# MCU.net
KiCad netlist of a schematic drawn in Altium Designer
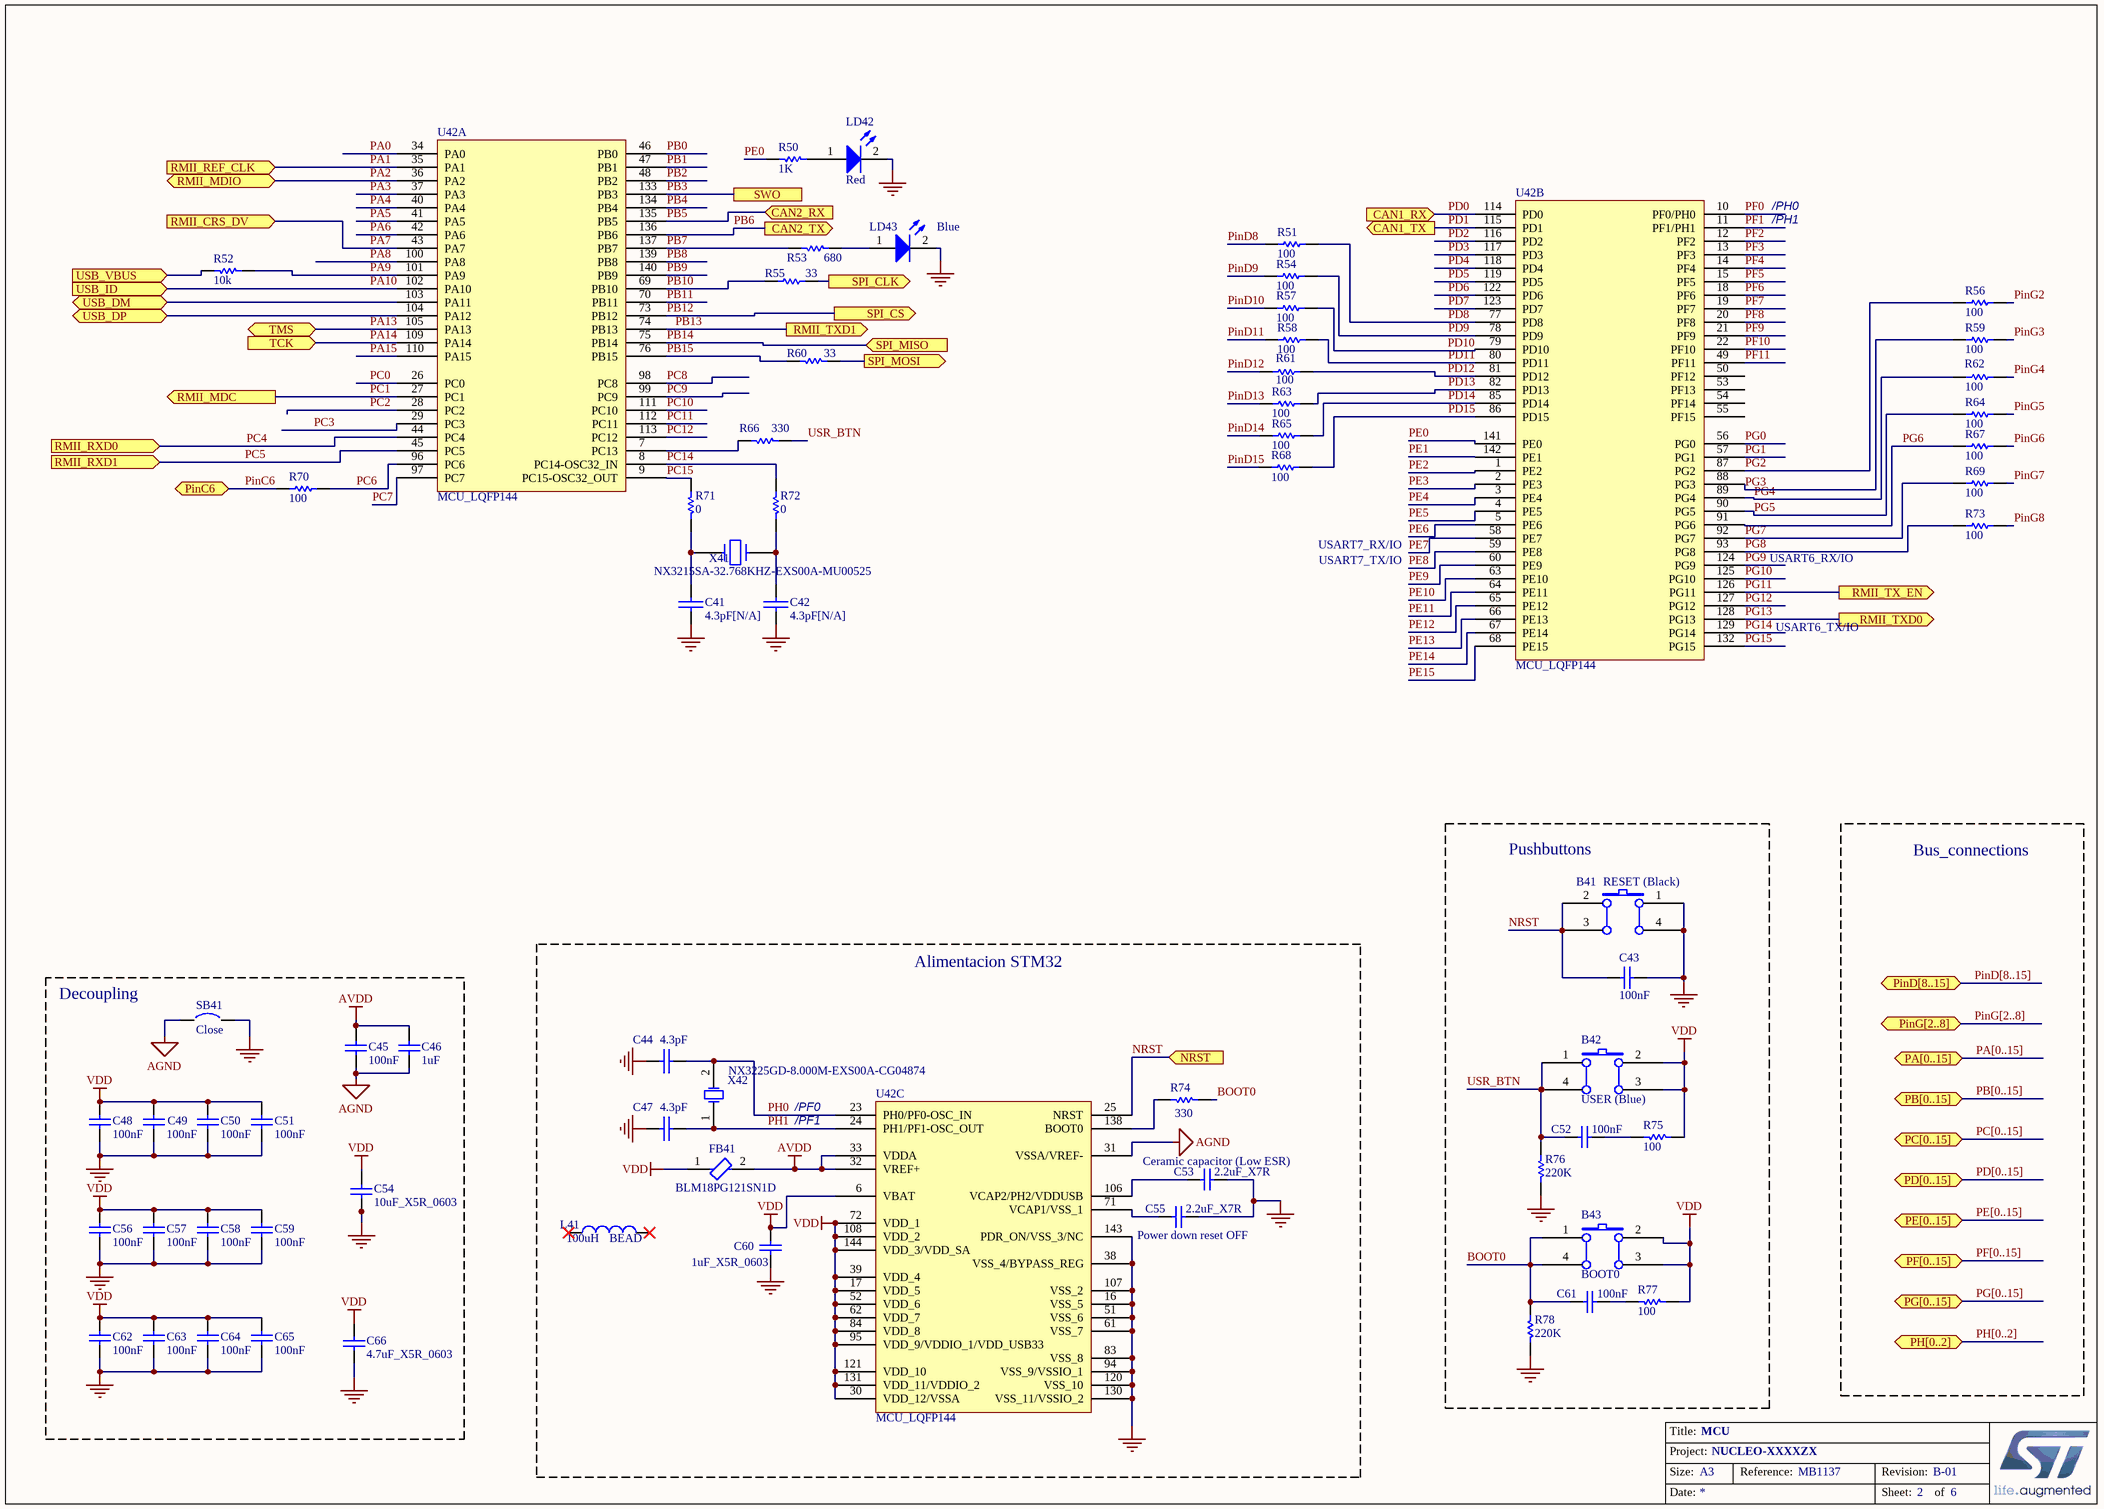
[diagram p0: MCU.SchDoc]

(export (version "E")
  (design (tool "Eeschema 10.0.6"))
  (components
    (comp (ref "B41")
      (value "RESET (Black)")
      (footprint "PB-6X6mm-Black")
      (description "SE PUSHBUTTON")
      (libsource (lib "Documents") (part "SW PUSHBUTTON"))
    )
    (comp (ref "B42")
      (value "USER (Blue)")
      (footprint "PB-6X6mm-Blue")
      (description "SE PUSHBUTTON")
      (libsource (lib "Documents") (part "SW PUSHBUTTON"))
    )
    (comp (ref "B43")
      (value "BOOT0")
      (footprint "PB-6X6mm-Blue")
      (description "SE PUSHBUTTON")
      (libsource (lib "Documents") (part "SW PUSHBUTTON"))
    )
    (comp (ref "C41")
      (value "4.3pF[N/A]")
      (footprint "0603C")
      (description "Capacitor")
      (libsource (lib "MB1137") (part "CAP"))
    )
    (comp (ref "C42")
      (value "4.3pF[N/A]")
      (footprint "0603C")
      (description "Capacitor")
      (libsource (lib "MB1137") (part "CAP"))
    )
    (comp (ref "C43")
      (value "100nF")
      (footprint "0603C")
      (description "Capacitor")
      (fields (field (name "PUBLISHER") "Altium Limited"))
      (libsource (lib "Miscellaneous Devices") (part "CAP"))
    )
    (comp (ref "C44")
      (value "4.3pF")
      (footprint "0603C")
      (description "Capacitor")
      (libsource (lib "MB1137") (part "CAP"))
    )
    (comp (ref "C45")
      (value "100nF")
      (footprint "0603C")
      (description "Capacitor")
      (fields (field (name "PUBLISHER") "Altium Limited"))
      (libsource (lib "Miscellaneous Devices") (part "Cap"))
    )
    (comp (ref "C46")
      (value "1uF")
      (footprint "0603C")
      (description "Capacitor")
      (fields (field (name "PUBLISHER") "Altium Limited"))
      (libsource (lib "Miscellaneous Devices") (part "Cap"))
    )
    (comp (ref "C47")
      (value "4.3pF")
      (footprint "0603C")
      (description "Capacitor")
      (libsource (lib "MB1137") (part "CAP"))
    )
    (comp (ref "C48")
      (value "100nF")
      (footprint "0603C")
      (description "Capacitor")
      (fields (field (name "PUBLISHER") "Altium Limited"))
      (libsource (lib "Miscellaneous Devices") (part "Cap"))
    )
    (comp (ref "C49")
      (value "100nF")
      (footprint "0603C")
      (description "Capacitor")
      (fields (field (name "PUBLISHER") "Altium Limited"))
      (libsource (lib "Miscellaneous Devices") (part "Cap"))
    )
    (comp (ref "C50")
      (value "100nF")
      (footprint "0603C")
      (description "Capacitor")
      (fields (field (name "PUBLISHER") "Altium Limited"))
      (libsource (lib "Miscellaneous Devices") (part "Cap"))
    )
    (comp (ref "C51")
      (value "100nF")
      (footprint "0603C")
      (description "Capacitor")
      (fields (field (name "PUBLISHER") "Altium Limited"))
      (libsource (lib "Miscellaneous Devices") (part "Cap"))
    )
    (comp (ref "C52")
      (value "100nF")
      (footprint "0603C")
      (description "Capacitor")
      (fields (field (name "PUBLISHER") "Altium Limited"))
      (libsource (lib "") (part "CAP_1"))
    )
    (comp (ref "C53")
      (value "2.2uF_X7R")
      (footprint "TAN-A")
      (description "Capacitor,2.2uF,16V, X7R,10%,0805,YAGEO")
      (libsource (lib "MCD_TOOLS") (part "Cap_2.2uF_X7R_10%_0805"))
    )
    (comp (ref "C54")
      (value "10uF_X5R_0603")
      (footprint "0603C")
      (description "0603  X5R 4.7uF")
      (fields (field (name "TOLERANCE") "10%"))
      (libsource (lib "MB963_1") (part "CAP SMD 0603  X5R 1µF 25V 10%"))
    )
    (comp (ref "C55")
      (value "2.2uF_X7R")
      (footprint "TAN-A")
      (description "Capacitor,2.2uF,16V, X7R,10%,0805,YAGEO")
      (libsource (lib "MCD_TOOLS") (part "Cap_2.2uF_X7R_10%_0805"))
    )
    (comp (ref "C56")
      (value "100nF")
      (footprint "0603C")
      (description "Capacitor")
      (fields (field (name "PUBLISHER") "Altium Limited"))
      (libsource (lib "Miscellaneous Devices") (part "Cap"))
    )
    (comp (ref "C57")
      (value "100nF")
      (footprint "0603C")
      (description "Capacitor")
      (fields (field (name "PUBLISHER") "Altium Limited"))
      (libsource (lib "Miscellaneous Devices") (part "Cap"))
    )
    (comp (ref "C58")
      (value "100nF")
      (footprint "0603C")
      (description "Capacitor")
      (fields (field (name "PUBLISHER") "Altium Limited"))
      (libsource (lib "Miscellaneous Devices") (part "Cap"))
    )
    (comp (ref "C59")
      (value "100nF")
      (footprint "0603C")
      (description "Capacitor")
      (fields (field (name "PUBLISHER") "Altium Limited"))
      (libsource (lib "Miscellaneous Devices") (part "Cap"))
    )
    (comp (ref "C60")
      (value "1uF_X5R_0603")
      (footprint "0603C")
      (description "0603  X5R 1µF")
      (fields (field (name "TOLERANCE") "10%"))
      (libsource (lib "MB963_1") (part "CAP SMD 0603  X5R 1µF 25V 10%"))
    )
    (comp (ref "C61")
      (value "100nF")
      (footprint "0603C")
      (description "Capacitor")
      (fields (field (name "PUBLISHER") "Altium Limited"))
      (libsource (lib "") (part "CAP_1"))
    )
    (comp (ref "C62")
      (value "100nF")
      (footprint "0603C")
      (description "Capacitor")
      (fields (field (name "PUBLISHER") "Altium Limited"))
      (libsource (lib "Miscellaneous Devices") (part "Cap"))
    )
    (comp (ref "C63")
      (value "100nF")
      (footprint "0603C")
      (description "Capacitor")
      (fields (field (name "PUBLISHER") "Altium Limited"))
      (libsource (lib "Miscellaneous Devices") (part "Cap"))
    )
    (comp (ref "C64")
      (value "100nF")
      (footprint "0603C")
      (description "Capacitor")
      (fields (field (name "PUBLISHER") "Altium Limited"))
      (libsource (lib "Miscellaneous Devices") (part "Cap"))
    )
    (comp (ref "C65")
      (value "100nF")
      (footprint "0603C")
      (description "Capacitor")
      (fields (field (name "PUBLISHER") "Altium Limited"))
      (libsource (lib "Miscellaneous Devices") (part "Cap"))
    )
    (comp (ref "C66")
      (value "4.7uF_X5R_0603")
      (footprint "0603C")
      (description "0603  X5R 4.7uF")
      (fields (field (name "TOLERANCE") "10%"))
      (libsource (lib "MB963_1") (part "CAP SMD 0603  X5R 1µF 25V 10%"))
    )
    (comp (ref "FB41")
      (value "BLM18PG121SN1D")
      (footprint "FP-BLM18-0_15-t0_8-IPC_A")
      (description "Chip Ferrite Bead, 0603, 120Ω @ 100MHz, 0.05Ω, 25%, 2A")
      (fields (field (name "TOLERANCE") "25%"))
      (libsource (lib "Altium Content Vault") (part "5f30dd21d616792df468990f7003faa"))
    )
    (comp (ref "L41")
      (value "BEAD")
      (description "Inductor")
      (fields (field (name "ALTIUM_VALUE") "100uH") (field (name "PUBLISHER") "Altium Limited"))
      (libsource (lib "Miscellaneous Devices") (part "Inductor"))
    )
    (comp (ref "LD42")
      (value "Red")
      (footprint "0603D-R")
      (description "Typical RED, GREEN, YELLOW, AMBER GaAs LED")
      (fields (field (name "PUBLISHER") "Altium Limited"))
      (libsource (lib "Miscellaneous Devices") (part "LED2"))
    )
    (comp (ref "LD43")
      (value "Blue")
      (footprint "0603D-B")
      (description "Typical RED, GREEN, YELLOW, AMBER GaAs LED")
      (fields (field (name "PUBLISHER") "Altium Limited"))
      (libsource (lib "Miscellaneous Devices") (part "LED2"))
    )
    (comp (ref "R50")
      (value "1K")
      (footprint "0603R")
      (description "Resistor")
      (fields (field (name "PUBLISHER") "Altium Limited"))
      (libsource (lib "Miscellaneous Devices") (part "Res1"))
    )
    (comp (ref "R51")
      (value "100")
      (footprint "0603R")
      (description "Resistor 0402 / 0603 / 0805")
      (libsource (lib "MB1137") (part "Resistor_ST"))
    )
    (comp (ref "R52")
      (value "10k")
      (footprint "0603R")
      (description "Resistor")
      (fields (field (name "PUBLISHER") "Altium Limited"))
      (libsource (lib "Miscellaneous Devices") (part "Res1"))
    )
    (comp (ref "R53")
      (value "680")
      (footprint "0603R")
      (description "Resistor")
      (fields (field (name "PUBLISHER") "Altium Limited"))
      (libsource (lib "Miscellaneous Devices") (part "Res1"))
    )
    (comp (ref "R54")
      (value "100")
      (footprint "0603R")
      (description "Resistor 0402 / 0603 / 0805")
      (libsource (lib "MB1137") (part "Resistor_ST"))
    )
    (comp (ref "R55")
      (value "33")
      (footprint "0603R")
      (description "Resistor")
      (fields (field (name "PUBLISHER") "Altium Limited"))
      (libsource (lib "MB1137") (part "Res1"))
    )
    (comp (ref "R56")
      (value "100")
      (footprint "0603R")
      (description "Resistor 0402 / 0603 / 0805")
      (libsource (lib "MB1137") (part "Resistor_ST"))
    )
    (comp (ref "R57")
      (value "100")
      (footprint "0603R")
      (description "Resistor 0402 / 0603 / 0805")
      (libsource (lib "MB1137") (part "Resistor_ST"))
    )
    (comp (ref "R58")
      (value "100")
      (footprint "0603R")
      (description "Resistor 0402 / 0603 / 0805")
      (libsource (lib "MB1137") (part "Resistor_ST"))
    )
    (comp (ref "R59")
      (value "100")
      (footprint "0603R")
      (description "Resistor 0402 / 0603 / 0805")
      (libsource (lib "MB1137") (part "Resistor_ST"))
    )
    (comp (ref "R60")
      (value "33")
      (footprint "0603R")
      (description "Resistor")
      (fields (field (name "PUBLISHER") "Altium Limited"))
      (libsource (lib "Miscellaneous Devices") (part "Res1"))
    )
    (comp (ref "R61")
      (value "100")
      (footprint "0603R")
      (description "Resistor 0402 / 0603 / 0805")
      (libsource (lib "MB1137") (part "Resistor_ST"))
    )
    (comp (ref "R62")
      (value "100")
      (footprint "0603R")
      (description "Resistor 0402 / 0603 / 0805")
      (libsource (lib "MB1137") (part "Resistor_ST"))
    )
    (comp (ref "R63")
      (value "100")
      (footprint "0603R")
      (description "Resistor 0402 / 0603 / 0805")
      (libsource (lib "MB1137") (part "Resistor_ST"))
    )
    (comp (ref "R64")
      (value "100")
      (footprint "0603R")
      (description "Resistor 0402 / 0603 / 0805")
      (libsource (lib "MB1137") (part "Resistor_ST"))
    )
    (comp (ref "R65")
      (value "100")
      (footprint "0603R")
      (description "Resistor 0402 / 0603 / 0805")
      (libsource (lib "MB1137") (part "Resistor_ST"))
    )
    (comp (ref "R66")
      (value "330")
      (footprint "0603R")
      (description "Resistor")
      (fields (field (name "PUBLISHER") "Altium Limited"))
      (libsource (lib "Miscellaneous Devices") (part "Res1"))
    )
    (comp (ref "R67")
      (value "100")
      (footprint "0603R")
      (description "Resistor 0402 / 0603 / 0805")
      (libsource (lib "MB1137") (part "Resistor_ST"))
    )
    (comp (ref "R68")
      (value "100")
      (footprint "0603R")
      (description "Resistor 0402 / 0603 / 0805")
      (libsource (lib "MB1137") (part "Resistor_ST"))
    )
    (comp (ref "R69")
      (value "100")
      (footprint "0603R")
      (description "Resistor 0402 / 0603 / 0805")
      (libsource (lib "MB1137") (part "Resistor_ST"))
    )
    (comp (ref "R70")
      (value "100")
      (footprint "0603R")
      (description "Resistor 0402 / 0603 / 0805")
      (libsource (lib "MB1137") (part "Resistor_ST"))
    )
    (comp (ref "R71")
      (value "0")
      (footprint "0603R")
      (description "Resistor")
      (fields (field (name "PUBLISHER") "Altium Limited"))
      (libsource (lib "Miscellaneous Devices") (part "Res1"))
    )
    (comp (ref "R72")
      (value "0")
      (footprint "0603R")
      (description "Resistor")
      (fields (field (name "PUBLISHER") "Altium Limited"))
      (libsource (lib "Miscellaneous Devices") (part "Res1"))
    )
    (comp (ref "R73")
      (value "100")
      (footprint "0603R")
      (description "Resistor 0402 / 0603 / 0805")
      (libsource (lib "MB1137") (part "Resistor_ST"))
    )
    (comp (ref "R74")
      (value "330")
      (footprint "0603R")
      (description "Resistor")
      (fields (field (name "PUBLISHER") "Altium Limited"))
      (libsource (lib "Miscellaneous Devices") (part "Res1"))
    )
    (comp (ref "R75")
      (value "100")
      (footprint "0603R")
      (description "Resistor")
      (fields (field (name "PUBLISHER") "Altium Limited"))
      (libsource (lib "Miscellaneous Devices") (part "Res1"))
    )
    (comp (ref "R76")
      (value "220K")
      (footprint "0603R")
      (description "Resistor")
      (fields (field (name "PUBLISHER") "Altium Limited"))
      (libsource (lib "Miscellaneous Devices") (part "res1"))
    )
    (comp (ref "R77")
      (value "100")
      (footprint "0603R")
      (description "Resistor")
      (fields (field (name "PUBLISHER") "Altium Limited"))
      (libsource (lib "Miscellaneous Devices") (part "Res1"))
    )
    (comp (ref "R78")
      (value "220K")
      (footprint "0603R")
      (description "Resistor")
      (fields (field (name "PUBLISHER") "Altium Limited"))
      (libsource (lib "Miscellaneous Devices") (part "res1"))
    )
    (comp (ref "SB41")
      (value "Close")
      (footprint "SB_0603")
      (description "Circuit Breaker")
      (fields (field (name "PUBLISHER") "Altium Limited"))
      (libsource (lib "MB1137") (part "Circuit Breaker"))
    )
    (comp (ref "U42")
      (value "MCU_LQFP144")
      (footprint "LQFP144_0R5_SKT - sin_zocalo_UWU")
      (libsource (lib "MB1137") (part "MCU_LQFP144"))
    )
    (comp (ref "X41")
      (value "NX3215SA-32.768KHZ-EXS00A-MU00525")
      (footprint "XTAL_2SM_3R2X1R5")
      (description "Crystal")
      (libsource (lib "MB1167") (part "CRYSTAL_32K"))
    )
    (comp (ref "X42")
      (value "NX3225GD-8.000M-EXS00A-CG04874")
      (footprint "OSC_2SM_3R2x2R5")
      (description "Crystal Oscillator")
      (fields (field (name "PUBLISHER") "Altium Limited"))
      (libsource (lib "MB963_1") (part "XTAL"))
    )
  )
  (nets
    (net (code "9") (name "/BOOT0") (class "Default")
      (node (ref "B43") (pin "1") (pinfunction "A0_1") (pintype "passive"))
      (node (ref "B43") (pin "4") (pinfunction "A1_4") (pintype "passive"))
      (node (ref "C61") (pin "2") (pinfunction "2_2") (pintype "passive"))
      (node (ref "R74") (pin "2") (pinfunction "2_2") (pintype "passive"))
      (node (ref "R78") (pin "1") (pinfunction "1_1") (pintype "passive"))
    )
    (net (code "10") (name "/NRST") (class "Default")
      (node (ref "B41") (pin "2") (pinfunction "B0_2") (pintype "passive"))
      (node (ref "B41") (pin "3") (pinfunction "B1_3") (pintype "passive"))
      (node (ref "C43") (pin "2") (pinfunction "2_2") (pintype "passive"))
      (node (ref "U42") (pin "25") (pinfunction "NRST_25") (pintype "passive"))
    )
    (net (code "11") (name "/PA0") (class "Default")
      (node (ref "U42") (pin "34") (pinfunction "PA0_34") (pintype "passive"))
    )
    (net (code "12") (name "/PA1") (class "Default")
      (node (ref "U42") (pin "35") (pinfunction "PA1_35") (pintype "passive"))
    )
    (net (code "13") (name "/PA2") (class "Default")
      (node (ref "U42") (pin "36") (pinfunction "PA2_36") (pintype "passive"))
    )
    (net (code "14") (name "/PA3") (class "Default")
      (node (ref "U42") (pin "37") (pinfunction "PA3_37") (pintype "passive"))
    )
    (net (code "15") (name "/PA4") (class "Default")
      (node (ref "U42") (pin "40") (pinfunction "PA4_40") (pintype "passive"))
    )
    (net (code "16") (name "/PA5") (class "Default")
      (node (ref "U42") (pin "41") (pinfunction "PA5_41") (pintype "passive"))
    )
    (net (code "17") (name "/PA6") (class "Default")
      (node (ref "U42") (pin "42") (pinfunction "PA6_42") (pintype "passive"))
    )
    (net (code "18") (name "/PA7") (class "Default")
      (node (ref "U42") (pin "43") (pinfunction "PA7_43") (pintype "passive"))
    )
    (net (code "19") (name "/PA8") (class "Default")
      (node (ref "U42") (pin "100") (pinfunction "PA8_100") (pintype "passive"))
    )
    (net (code "20") (name "/PA9") (class "Default")
      (node (ref "R52") (pin "2") (pinfunction "2_2") (pintype "passive"))
      (node (ref "U42") (pin "101") (pinfunction "PA9_101") (pintype "passive"))
    )
    (net (code "21") (name "/PA10") (class "Default")
      (node (ref "U42") (pin "102") (pinfunction "PA10_102") (pintype "passive"))
    )
    (net (code "22") (name "/PA13") (class "Default")
      (node (ref "U42") (pin "105") (pinfunction "PA13_105") (pintype "passive"))
    )
    (net (code "23") (name "/PA14") (class "Default")
      (node (ref "U42") (pin "109") (pinfunction "PA14_109") (pintype "passive"))
    )
    (net (code "24") (name "/PA15") (class "Default")
      (node (ref "U42") (pin "110") (pinfunction "PA15_110") (pintype "passive"))
    )
    (net (code "26") (name "/PB0") (class "Default")
      (node (ref "U42") (pin "46") (pinfunction "PB0_46") (pintype "passive"))
    )
    (net (code "27") (name "/PB1") (class "Default")
      (node (ref "U42") (pin "47") (pinfunction "PB1_47") (pintype "passive"))
    )
    (net (code "28") (name "/PB2") (class "Default")
      (node (ref "U42") (pin "48") (pinfunction "PB2_48") (pintype "passive"))
    )
    (net (code "29") (name "/PB3") (class "Default")
      (node (ref "U42") (pin "133") (pinfunction "PB3_133") (pintype "passive"))
    )
    (net (code "30") (name "/PB4") (class "Default")
      (node (ref "U42") (pin "134") (pinfunction "PB4_134") (pintype "passive"))
    )
    (net (code "31") (name "/PB5") (class "Default")
      (node (ref "U42") (pin "135") (pinfunction "PB5_135") (pintype "passive"))
    )
    (net (code "32") (name "/PB6") (class "Default")
      (node (ref "U42") (pin "136") (pinfunction "PB6_136") (pintype "passive"))
    )
    (net (code "33") (name "/PB7") (class "Default")
      (node (ref "R53") (pin "1") (pinfunction "1_1") (pintype "passive"))
      (node (ref "U42") (pin "137") (pinfunction "PB7_137") (pintype "passive"))
    )
    (net (code "34") (name "/PB8") (class "Default")
      (node (ref "U42") (pin "139") (pinfunction "PB8_139") (pintype "passive"))
    )
    (net (code "35") (name "/PB9") (class "Default")
      (node (ref "U42") (pin "140") (pinfunction "PB9_140") (pintype "passive"))
    )
    (net (code "36") (name "/PB10") (class "Default")
      (node (ref "R55") (pin "1") (pinfunction "1_1") (pintype "passive"))
      (node (ref "U42") (pin "69") (pinfunction "PB10_69") (pintype "passive"))
    )
    (net (code "37") (name "/PB11") (class "Default")
      (node (ref "U42") (pin "70") (pinfunction "PB11_70") (pintype "passive"))
    )
    (net (code "38") (name "/PB12") (class "Default")
      (node (ref "U42") (pin "73") (pinfunction "PB12_73") (pintype "passive"))
    )
    (net (code "39") (name "/PB13") (class "Default")
      (node (ref "U42") (pin "74") (pinfunction "PB13_74") (pintype "passive"))
    )
    (net (code "40") (name "/PB14") (class "Default")
      (node (ref "U42") (pin "75") (pinfunction "PB14_75") (pintype "passive"))
    )
    (net (code "41") (name "/PB15") (class "Default")
      (node (ref "R60") (pin "1") (pinfunction "1_1") (pintype "passive"))
      (node (ref "U42") (pin "76") (pinfunction "PB15_76") (pintype "passive"))
    )
    (net (code "43") (name "/PC0") (class "Default")
      (node (ref "U42") (pin "26") (pinfunction "PC0_26") (pintype "passive"))
    )
    (net (code "44") (name "/PC1") (class "Default")
      (node (ref "U42") (pin "27") (pinfunction "PC1_27") (pintype "passive"))
    )
    (net (code "45") (name "/PC2") (class "Default")
      (node (ref "U42") (pin "28") (pinfunction "PC2_28") (pintype "passive"))
    )
    (net (code "46") (name "/PC3") (class "Default")
      (node (ref "U42") (pin "29") (pinfunction "PC3_29") (pintype "passive"))
    )
    (net (code "47") (name "/PC4") (class "Default")
      (node (ref "U42") (pin "44") (pinfunction "PC4_44") (pintype "passive"))
    )
    (net (code "48") (name "/PC5") (class "Default")
      (node (ref "U42") (pin "45") (pinfunction "PC5_45") (pintype "passive"))
    )
    (net (code "49") (name "/PC6") (class "Default")
      (node (ref "R70") (pin "2") (pinfunction "2_2") (pintype "passive"))
      (node (ref "U42") (pin "96") (pinfunction "PC6_96") (pintype "passive"))
    )
    (net (code "50") (name "/PC7") (class "Default")
      (node (ref "U42") (pin "97") (pinfunction "PC7_97") (pintype "passive"))
    )
    (net (code "51") (name "/PC8") (class "Default")
      (node (ref "U42") (pin "98") (pinfunction "PC8_98") (pintype "passive"))
    )
    (net (code "52") (name "/PC9") (class "Default")
      (node (ref "U42") (pin "99") (pinfunction "PC9_99") (pintype "passive"))
    )
    (net (code "53") (name "/PC10") (class "Default")
      (node (ref "U42") (pin "111") (pinfunction "PC10_111") (pintype "passive"))
    )
    (net (code "54") (name "/PC11") (class "Default")
      (node (ref "U42") (pin "112") (pinfunction "PC11_112") (pintype "passive"))
    )
    (net (code "55") (name "/PC12") (class "Default")
      (node (ref "U42") (pin "113") (pinfunction "PC12_113") (pintype "passive"))
    )
    (net (code "56") (name "/PC14") (class "Default")
      (node (ref "R72") (pin "2") (pinfunction "2_2") (pintype "passive"))
      (node (ref "U42") (pin "8") (pinfunction "PC14-OSC32_IN_8") (pintype "passive"))
    )
    (net (code "57") (name "/PC15") (class "Default")
      (node (ref "R71") (pin "2") (pinfunction "2_2") (pintype "passive"))
      (node (ref "U42") (pin "9") (pinfunction "PC15-OSC32_OUT_9") (pintype "passive"))
    )
    (net (code "59") (name "/PD0") (class "Default")
      (node (ref "U42") (pin "114") (pinfunction "PD0_114") (pintype "passive"))
    )
    (net (code "60") (name "/PD1") (class "Default")
      (node (ref "U42") (pin "115") (pinfunction "PD1_115") (pintype "passive"))
    )
    (net (code "61") (name "/PD2") (class "Default")
      (node (ref "U42") (pin "116") (pinfunction "PD2_116") (pintype "passive"))
    )
    (net (code "62") (name "/PD3") (class "Default")
      (node (ref "U42") (pin "117") (pinfunction "PD3_117") (pintype "passive"))
    )
    (net (code "63") (name "/PD4") (class "Default")
      (node (ref "U42") (pin "118") (pinfunction "PD4_118") (pintype "passive"))
    )
    (net (code "64") (name "/PD5") (class "Default")
      (node (ref "U42") (pin "119") (pinfunction "PD5_119") (pintype "passive"))
    )
    (net (code "65") (name "/PD6") (class "Default")
      (node (ref "U42") (pin "122") (pinfunction "PD6_122") (pintype "passive"))
    )
    (net (code "66") (name "/PD7") (class "Default")
      (node (ref "U42") (pin "123") (pinfunction "PD7_123") (pintype "passive"))
    )
    (net (code "67") (name "/PD8") (class "Default")
      (node (ref "R51") (pin "1") (pinfunction "1_1") (pintype "passive"))
      (node (ref "U42") (pin "77") (pinfunction "PD8_77") (pintype "passive"))
    )
    (net (code "68") (name "/PD9") (class "Default")
      (node (ref "R54") (pin "1") (pinfunction "1_1") (pintype "passive"))
      (node (ref "U42") (pin "78") (pinfunction "PD9_78") (pintype "passive"))
    )
    (net (code "69") (name "/PD10") (class "Default")
      (node (ref "R57") (pin "1") (pinfunction "1_1") (pintype "passive"))
      (node (ref "U42") (pin "79") (pinfunction "PD10_79") (pintype "passive"))
    )
    (net (code "70") (name "/PD11") (class "Default")
      (node (ref "R58") (pin "1") (pinfunction "1_1") (pintype "passive"))
      (node (ref "U42") (pin "80") (pinfunction "PD11_80") (pintype "passive"))
    )
    (net (code "71") (name "/PD12") (class "Default")
      (node (ref "R61") (pin "1") (pinfunction "1_1") (pintype "passive"))
      (node (ref "U42") (pin "81") (pinfunction "PD12_81") (pintype "passive"))
    )
    (net (code "72") (name "/PD13") (class "Default")
      (node (ref "R63") (pin "2") (pinfunction "2_2") (pintype "passive"))
      (node (ref "U42") (pin "82") (pinfunction "PD13_82") (pintype "passive"))
    )
    (net (code "73") (name "/PD14") (class "Default")
      (node (ref "R65") (pin "1") (pinfunction "1_1") (pintype "passive"))
      (node (ref "U42") (pin "85") (pinfunction "PD14_85") (pintype "passive"))
    )
    (net (code "74") (name "/PD15") (class "Default")
      (node (ref "R68") (pin "2") (pinfunction "2_2") (pintype "passive"))
      (node (ref "U42") (pin "86") (pinfunction "PD15_86") (pintype "passive"))
    )
    (net (code "76") (name "/PE0") (class "Default")
      (node (ref "R50") (pin "2") (pinfunction "2_2") (pintype "passive"))
      (node (ref "U42") (pin "141") (pinfunction "PE0_141") (pintype "passive"))
    )
    (net (code "77") (name "/PE1") (class "Default")
      (node (ref "U42") (pin "142") (pinfunction "PE1_142") (pintype "passive"))
    )
    (net (code "78") (name "/PE2") (class "Default")
      (node (ref "U42") (pin "1") (pinfunction "PE2_1") (pintype "passive"))
    )
    (net (code "79") (name "/PE3") (class "Default")
      (node (ref "U42") (pin "2") (pinfunction "PE3_2") (pintype "passive"))
    )
    (net (code "80") (name "/PE4") (class "Default")
      (node (ref "U42") (pin "3") (pinfunction "PE4_3") (pintype "passive"))
    )
    (net (code "81") (name "/PE5") (class "Default")
      (node (ref "U42") (pin "4") (pinfunction "PE5_4") (pintype "passive"))
    )
    (net (code "82") (name "/PE6") (class "Default")
      (node (ref "U42") (pin "5") (pinfunction "PE6_5") (pintype "passive"))
    )
    (net (code "83") (name "/PE7") (class "Default")
      (node (ref "U42") (pin "58") (pinfunction "PE7_58") (pintype "passive"))
    )
    (net (code "84") (name "/PE8") (class "Default")
      (node (ref "U42") (pin "59") (pinfunction "PE8_59") (pintype "passive"))
    )
    (net (code "85") (name "/PE9") (class "Default")
      (node (ref "U42") (pin "60") (pinfunction "PE9_60") (pintype "passive"))
    )
    (net (code "86") (name "/PE10") (class "Default")
      (node (ref "U42") (pin "63") (pinfunction "PE10_63") (pintype "passive"))
    )
    (net (code "87") (name "/PE11") (class "Default")
      (node (ref "U42") (pin "64") (pinfunction "PE11_64") (pintype "passive"))
    )
    (net (code "88") (name "/PE12") (class "Default")
      (node (ref "U42") (pin "65") (pinfunction "PE12_65") (pintype "passive"))
    )
    (net (code "89") (name "/PE13") (class "Default")
      (node (ref "U42") (pin "66") (pinfunction "PE13_66") (pintype "passive"))
    )
    (net (code "90") (name "/PE14") (class "Default")
      (node (ref "U42") (pin "67") (pinfunction "PE14_67") (pintype "passive"))
    )
    (net (code "91") (name "/PE15") (class "Default")
      (node (ref "U42") (pin "68") (pinfunction "PE15_68") (pintype "passive"))
    )
    (net (code "93") (name "/PF0") (class "Default")
      (node (ref "U42") (pin "10") (pinfunction "PF0/PH0_10") (pintype "passive"))
    )
    (net (code "94") (name "/PF1") (class "Default")
      (node (ref "U42") (pin "11") (pinfunction "PF1/PH1_11") (pintype "passive"))
    )
    (net (code "95") (name "/PF2") (class "Default")
      (node (ref "U42") (pin "12") (pinfunction "PF2_12") (pintype "passive"))
    )
    (net (code "96") (name "/PF3") (class "Default")
      (node (ref "U42") (pin "13") (pinfunction "PF3_13") (pintype "passive"))
    )
    (net (code "97") (name "/PF4") (class "Default")
      (node (ref "U42") (pin "14") (pinfunction "PF4_14") (pintype "passive"))
    )
    (net (code "98") (name "/PF5") (class "Default")
      (node (ref "U42") (pin "15") (pinfunction "PF5_15") (pintype "passive"))
    )
    (net (code "99") (name "/PF6") (class "Default")
      (node (ref "U42") (pin "18") (pinfunction "PF6_18") (pintype "passive"))
    )
    (net (code "100") (name "/PF7") (class "Default")
      (node (ref "U42") (pin "19") (pinfunction "PF7_19") (pintype "passive"))
    )
    (net (code "101") (name "/PF8") (class "Default")
      (node (ref "U42") (pin "20") (pinfunction "PF8_20") (pintype "passive"))
    )
    (net (code "102") (name "/PF9") (class "Default")
      (node (ref "U42") (pin "21") (pinfunction "PF9_21") (pintype "passive"))
    )
    (net (code "103") (name "/PF10") (class "Default")
      (node (ref "U42") (pin "22") (pinfunction "PF10_22") (pintype "passive"))
    )
    (net (code "104") (name "/PF11") (class "Default")
      (node (ref "U42") (pin "49") (pinfunction "PF11_49") (pintype "passive"))
    )
    (net (code "106") (name "/PG0") (class "Default")
      (node (ref "U42") (pin "56") (pinfunction "PG0_56") (pintype "passive"))
    )
    (net (code "107") (name "/PG1") (class "Default")
      (node (ref "U42") (pin "57") (pinfunction "PG1_57") (pintype "passive"))
    )
    (net (code "108") (name "/PG2") (class "Default")
      (node (ref "R56") (pin "2") (pinfunction "2_2") (pintype "passive"))
      (node (ref "U42") (pin "87") (pinfunction "PG2_87") (pintype "passive"))
    )
    (net (code "109") (name "/PG3") (class "Default")
      (node (ref "R59") (pin "2") (pinfunction "2_2") (pintype "passive"))
      (node (ref "U42") (pin "88") (pinfunction "PG3_88") (pintype "passive"))
    )
    (net (code "110") (name "/PG4") (class "Default")
      (node (ref "R62") (pin "1") (pinfunction "1_1") (pintype "passive"))
      (node (ref "U42") (pin "89") (pinfunction "PG4_89") (pintype "passive"))
    )
    (net (code "111") (name "/PG5") (class "Default")
      (node (ref "R64") (pin "1") (pinfunction "1_1") (pintype "passive"))
      (node (ref "U42") (pin "90") (pinfunction "PG5_90") (pintype "passive"))
    )
    (net (code "112") (name "/PG6") (class "Default")
      (node (ref "R67") (pin "2") (pinfunction "2_2") (pintype "passive"))
      (node (ref "U42") (pin "91") (pinfunction "PG6_91") (pintype "passive"))
    )
    (net (code "113") (name "/PG7") (class "Default")
      (node (ref "R69") (pin "2") (pinfunction "2_2") (pintype "passive"))
      (node (ref "U42") (pin "92") (pinfunction "PG7_92") (pintype "passive"))
    )
    (net (code "114") (name "/PG8") (class "Default")
      (node (ref "R73") (pin "2") (pinfunction "2_2") (pintype "passive"))
      (node (ref "U42") (pin "93") (pinfunction "PG8_93") (pintype "passive"))
    )
    (net (code "115") (name "/PG9") (class "Default")
      (node (ref "U42") (pin "124") (pinfunction "PG9_124") (pintype "passive"))
    )
    (net (code "116") (name "/PG10") (class "Default")
      (node (ref "U42") (pin "125") (pinfunction "PG10_125") (pintype "passive"))
    )
    (net (code "117") (name "/PG11") (class "Default")
      (node (ref "U42") (pin "126") (pinfunction "PG11_126") (pintype "passive"))
    )
    (net (code "118") (name "/PG12") (class "Default")
      (node (ref "U42") (pin "127") (pinfunction "PG12_127") (pintype "passive"))
    )
    (net (code "119") (name "/PG13") (class "Default")
      (node (ref "U42") (pin "128") (pinfunction "PG13_128") (pintype "passive"))
    )
    (net (code "120") (name "/PG14") (class "Default")
      (node (ref "U42") (pin "129") (pinfunction "PG14_129") (pintype "passive"))
    )
    (net (code "121") (name "/PG15") (class "Default")
      (node (ref "U42") (pin "132") (pinfunction "PG15_132") (pintype "passive"))
    )
    (net (code "123") (name "/PH0") (class "Default")
      (node (ref "C44") (pin "1") (pinfunction "1_1") (pintype "passive"))
      (node (ref "U42") (pin "23") (pinfunction "PH0/PF0-OSC_IN_23") (pintype "passive"))
      (node (ref "X42") (pin "2") (pinfunction "OSC2_2") (pintype "passive"))
    )
    (net (code "124") (name "/PH1") (class "Default")
      (node (ref "C47") (pin "1") (pinfunction "1_1") (pintype "passive"))
      (node (ref "U42") (pin "24") (pinfunction "PH1/PF1-OSC_OUT_24") (pintype "passive"))
      (node (ref "X42") (pin "1") (pinfunction "OSC1_1") (pintype "passive"))
    )
    (net (code "126") (name "/PinC6") (class "Default")
      (node (ref "R70") (pin "1") (pinfunction "1_1") (pintype "passive"))
    )
    (net (code "127") (name "/PinD8") (class "Default")
      (node (ref "R51") (pin "2") (pinfunction "2_2") (pintype "passive"))
    )
    (net (code "128") (name "/PinD9") (class "Default")
      (node (ref "R54") (pin "2") (pinfunction "2_2") (pintype "passive"))
    )
    (net (code "129") (name "/PinD10") (class "Default")
      (node (ref "R57") (pin "2") (pinfunction "2_2") (pintype "passive"))
    )
    (net (code "130") (name "/PinD11") (class "Default")
      (node (ref "R58") (pin "2") (pinfunction "2_2") (pintype "passive"))
    )
    (net (code "131") (name "/PinD12") (class "Default")
      (node (ref "R61") (pin "2") (pinfunction "2_2") (pintype "passive"))
    )
    (net (code "132") (name "/PinD13") (class "Default")
      (node (ref "R63") (pin "1") (pinfunction "1_1") (pintype "passive"))
    )
    (net (code "133") (name "/PinD14") (class "Default")
      (node (ref "R65") (pin "2") (pinfunction "2_2") (pintype "passive"))
    )
    (net (code "134") (name "/PinD15") (class "Default")
      (node (ref "R68") (pin "1") (pinfunction "1_1") (pintype "passive"))
    )
    (net (code "136") (name "/PinG2") (class "Default")
      (node (ref "R56") (pin "1") (pinfunction "1_1") (pintype "passive"))
    )
    (net (code "137") (name "/PinG3") (class "Default")
      (node (ref "R59") (pin "1") (pinfunction "1_1") (pintype "passive"))
    )
    (net (code "138") (name "/PinG4") (class "Default")
      (node (ref "R62") (pin "2") (pinfunction "2_2") (pintype "passive"))
    )
    (net (code "139") (name "/PinG5") (class "Default")
      (node (ref "R64") (pin "2") (pinfunction "2_2") (pintype "passive"))
    )
    (net (code "140") (name "/PinG6") (class "Default")
      (node (ref "R67") (pin "1") (pinfunction "1_1") (pintype "passive"))
    )
    (net (code "141") (name "/PinG7") (class "Default")
      (node (ref "R69") (pin "1") (pinfunction "1_1") (pintype "passive"))
    )
    (net (code "142") (name "/PinG8") (class "Default")
      (node (ref "R73") (pin "1") (pinfunction "1_1") (pintype "passive"))
    )
    (net (code "144") (name "/SPI_CLK") (class "Default")
      (node (ref "R55") (pin "2") (pinfunction "2_2") (pintype "passive"))
    )
    (net (code "145") (name "/SPI_MOSI") (class "Default")
      (node (ref "R60") (pin "2") (pinfunction "2_2") (pintype "passive"))
    )
    (net (code "146") (name "/USB_DM") (class "Default")
      (node (ref "U42") (pin "103") (pinfunction "PA11_103") (pintype "passive"))
    )
    (net (code "147") (name "/USB_DP") (class "Default")
      (node (ref "U42") (pin "104") (pinfunction "PA12_104") (pintype "passive"))
    )
    (net (code "148") (name "/USB_VBUS") (class "Default")
      (node (ref "R52") (pin "1") (pinfunction "1_1") (pintype "passive"))
    )
    (net (code "149") (name "/USR_BTN") (class "Default")
      (node (ref "B42") (pin "1") (pinfunction "A0_1") (pintype "passive"))
      (node (ref "B42") (pin "4") (pinfunction "A1_4") (pintype "passive"))
      (node (ref "C52") (pin "2") (pinfunction "2_2") (pintype "passive"))
      (node (ref "R66") (pin "1") (pinfunction "1_1") (pintype "passive"))
      (node (ref "R76") (pin "1") (pinfunction "1_1") (pintype "passive"))
    )
    (net (code "150") (name "AGND") (class "Default")
      (node (ref "C45") (pin "2") (pinfunction "2_2") (pintype "passive"))
      (node (ref "C46") (pin "2") (pinfunction "2_2") (pintype "passive"))
      (node (ref "SB41") (pin "1") (pinfunction "1_1") (pintype "passive"))
      (node (ref "U42") (pin "31") (pinfunction "VSSA/VREF-_31") (pintype "passive"))
    )
    (net (code "151") (name "AVDD") (class "Default")
      (node (ref "C45") (pin "1") (pinfunction "1_1") (pintype "passive"))
      (node (ref "C46") (pin "1") (pinfunction "1_1") (pintype "passive"))
      (node (ref "FB41") (pin "2") (pinfunction "2_2") (pintype "passive"))
      (node (ref "U42") (pin "32") (pinfunction "VREF+_32") (pintype "passive"))
      (node (ref "U42") (pin "33") (pinfunction "VDDA_33") (pintype "passive"))
    )
    (net (code "152") (name "GND") (class "Default")
      (node (ref "B41") (pin "1") (pinfunction "A0_1") (pintype "passive"))
      (node (ref "B41") (pin "4") (pinfunction "A1_4") (pintype "passive"))
      (node (ref "C41") (pin "2") (pinfunction "2_2") (pintype "passive"))
      (node (ref "C42") (pin "2") (pinfunction "2_2") (pintype "passive"))
      (node (ref "C43") (pin "1") (pinfunction "1_1") (pintype "passive"))
      (node (ref "C44") (pin "2") (pinfunction "2_2") (pintype "passive"))
      (node (ref "C47") (pin "2") (pinfunction "2_2") (pintype "passive"))
      (node (ref "C48") (pin "2") (pinfunction "2_2") (pintype "passive"))
      (node (ref "C49") (pin "2") (pinfunction "2_2") (pintype "passive"))
      (node (ref "C50") (pin "2") (pinfunction "2_2") (pintype "passive"))
      (node (ref "C51") (pin "2") (pinfunction "2_2") (pintype "passive"))
      (node (ref "C53") (pin "2") (pinfunction "2_2") (pintype "passive"))
      (node (ref "C54") (pin "2") (pinfunction "2_2") (pintype "passive"))
      (node (ref "C55") (pin "2") (pinfunction "2_2") (pintype "passive"))
      (node (ref "C56") (pin "2") (pinfunction "2_2") (pintype "passive"))
      (node (ref "C57") (pin "2") (pinfunction "2_2") (pintype "passive"))
      (node (ref "C58") (pin "2") (pinfunction "2_2") (pintype "passive"))
      (node (ref "C59") (pin "2") (pinfunction "2_2") (pintype "passive"))
      (node (ref "C60") (pin "2") (pinfunction "2_2") (pintype "passive"))
      (node (ref "C62") (pin "2") (pinfunction "2_2") (pintype "passive"))
      (node (ref "C63") (pin "2") (pinfunction "2_2") (pintype "passive"))
      (node (ref "C64") (pin "2") (pinfunction "2_2") (pintype "passive"))
      (node (ref "C65") (pin "2") (pinfunction "2_2") (pintype "passive"))
      (node (ref "C66") (pin "2") (pinfunction "2_2") (pintype "passive"))
      (node (ref "LD42") (pin "2") (pinfunction "K_2") (pintype "passive"))
      (node (ref "LD43") (pin "2") (pinfunction "K_2") (pintype "passive"))
      (node (ref "R76") (pin "2") (pinfunction "2_2") (pintype "passive"))
      (node (ref "R78") (pin "2") (pinfunction "2_2") (pintype "passive"))
      (node (ref "SB41") (pin "2") (pinfunction "2_2") (pintype "passive"))
      (node (ref "U42") (pin "107") (pinfunction "VSS_2_107") (pintype "passive"))
      (node (ref "U42") (pin "120") (pinfunction "VSS_10_120") (pintype "passive"))
      (node (ref "U42") (pin "130") (pinfunction "VSS_11/VSSIO_2_130") (pintype "passive"))
      (node (ref "U42") (pin "143") (pinfunction "PDR_ON/VSS_3/NC_143") (pintype "passive"))
      (node (ref "U42") (pin "16") (pinfunction "VSS_5_16") (pintype "passive"))
      (node (ref "U42") (pin "38") (pinfunction "VSS_4/BYPASS_REG_38") (pintype "passive"))
      (node (ref "U42") (pin "51") (pinfunction "VSS_6_51") (pintype "passive"))
      (node (ref "U42") (pin "61") (pinfunction "VSS_7_61") (pintype "passive"))
      (node (ref "U42") (pin "83") (pinfunction "VSS_8_83") (pintype "passive"))
      (node (ref "U42") (pin "94") (pinfunction "VSS_9/VSSIO_1_94") (pintype "passive"))
    )
    (net (code "153") (name "Net-(C41-Pad1)") (class "Default")
      (node (ref "C41") (pin "1") (pinfunction "1_1") (pintype "passive"))
      (node (ref "R71") (pin "1") (pinfunction "1_1") (pintype "passive"))
      (node (ref "X41") (pin "1") (pinfunction "1_1") (pintype "passive"))
    )
    (net (code "154") (name "Net-(C42-Pad1)") (class "Default")
      (node (ref "C42") (pin "1") (pinfunction "1_1") (pintype "passive"))
      (node (ref "R72") (pin "1") (pinfunction "1_1") (pintype "passive"))
      (node (ref "X41") (pin "2") (pinfunction "2_2") (pintype "passive"))
    )
    (net (code "155") (name "Net-(C52-Pad1)") (class "Default")
      (node (ref "C52") (pin "1") (pinfunction "1_1") (pintype "passive"))
      (node (ref "R75") (pin "2") (pinfunction "2_2") (pintype "passive"))
    )
    (net (code "156") (name "Net-(C61-Pad1)") (class "Default")
      (node (ref "C61") (pin "1") (pinfunction "1_1") (pintype "passive"))
      (node (ref "R77") (pin "2") (pinfunction "2_2") (pintype "passive"))
    )
    (net (code "157") (name "Net-(LD42-A)") (class "Default")
      (node (ref "LD42") (pin "1") (pinfunction "A_1") (pintype "passive"))
      (node (ref "R50") (pin "1") (pinfunction "1_1") (pintype "passive"))
    )
    (net (code "158") (name "Net-(LD43-A)") (class "Default")
      (node (ref "LD43") (pin "1") (pinfunction "A_1") (pintype "passive"))
      (node (ref "R53") (pin "2") (pinfunction "2_2") (pintype "passive"))
    )
    (net (code "159") (name "Net-(U42A-PC13)") (class "Default")
      (node (ref "R66") (pin "2") (pinfunction "2_2") (pintype "passive"))
      (node (ref "U42") (pin "7") (pinfunction "PC13_7") (pintype "passive"))
    )
    (net (code "160") (name "Net-(U42C-BOOT0)") (class "Default")
      (node (ref "R74") (pin "1") (pinfunction "1_1") (pintype "passive"))
      (node (ref "U42") (pin "138") (pinfunction "BOOT0_138") (pintype "passive"))
    )
    (net (code "161") (name "Net-(U42C-VCAP1{slash}VSS_1)") (class "Default")
      (node (ref "C55") (pin "1") (pinfunction "1_1") (pintype "passive"))
      (node (ref "U42") (pin "71") (pinfunction "VCAP1/VSS_1_71") (pintype "passive"))
    )
    (net (code "162") (name "Net-(U42C-VCAP2{slash}PH2{slash}VDDUSB)") (class "Default")
      (node (ref "C53") (pin "1") (pinfunction "1_1") (pintype "passive"))
      (node (ref "U42") (pin "106") (pinfunction "VCAP2/PH2/VDDUSB_106") (pintype "passive"))
    )
    (net (code "163") (name "VDD") (class "Default")
      (node (ref "B42") (pin "2") (pinfunction "B0_2") (pintype "passive"))
      (node (ref "B42") (pin "3") (pinfunction "B1_3") (pintype "passive"))
      (node (ref "B43") (pin "2") (pinfunction "B0_2") (pintype "passive"))
      (node (ref "B43") (pin "3") (pinfunction "B1_3") (pintype "passive"))
      (node (ref "C48") (pin "1") (pinfunction "1_1") (pintype "passive"))
      (node (ref "C49") (pin "1") (pinfunction "1_1") (pintype "passive"))
      (node (ref "C50") (pin "1") (pinfunction "1_1") (pintype "passive"))
      (node (ref "C51") (pin "1") (pinfunction "1_1") (pintype "passive"))
      (node (ref "C54") (pin "1") (pinfunction "1_1") (pintype "passive"))
      (node (ref "C56") (pin "1") (pinfunction "1_1") (pintype "passive"))
      (node (ref "C57") (pin "1") (pinfunction "1_1") (pintype "passive"))
      (node (ref "C58") (pin "1") (pinfunction "1_1") (pintype "passive"))
      (node (ref "C59") (pin "1") (pinfunction "1_1") (pintype "passive"))
      (node (ref "C60") (pin "1") (pinfunction "1_1") (pintype "passive"))
      (node (ref "C62") (pin "1") (pinfunction "1_1") (pintype "passive"))
      (node (ref "C63") (pin "1") (pinfunction "1_1") (pintype "passive"))
      (node (ref "C64") (pin "1") (pinfunction "1_1") (pintype "passive"))
      (node (ref "C65") (pin "1") (pinfunction "1_1") (pintype "passive"))
      (node (ref "C66") (pin "1") (pinfunction "1_1") (pintype "passive"))
      (node (ref "FB41") (pin "1") (pinfunction "1_1") (pintype "passive"))
      (node (ref "R75") (pin "1") (pinfunction "1_1") (pintype "passive"))
      (node (ref "R77") (pin "1") (pinfunction "1_1") (pintype "passive"))
      (node (ref "U42") (pin "108") (pinfunction "VDD_2_108") (pintype "passive"))
      (node (ref "U42") (pin "121") (pinfunction "VDD_10_121") (pintype "passive"))
      (node (ref "U42") (pin "131") (pinfunction "VDD_11/VDDIO_2_131") (pintype "passive"))
      (node (ref "U42") (pin "144") (pinfunction "VDD_3/VDD_SA_144") (pintype "passive"))
      (node (ref "U42") (pin "17") (pinfunction "VDD_5_17") (pintype "passive"))
      (node (ref "U42") (pin "30") (pinfunction "VDD_12/VSSA_30") (pintype "passive"))
      (node (ref "U42") (pin "39") (pinfunction "VDD_4_39") (pintype "passive"))
      (node (ref "U42") (pin "52") (pinfunction "VDD_6_52") (pintype "passive"))
      (node (ref "U42") (pin "6") (pinfunction "VBAT_6") (pintype "passive"))
      (node (ref "U42") (pin "62") (pinfunction "VDD_7_62") (pintype "passive"))
      (node (ref "U42") (pin "72") (pinfunction "VDD_1_72") (pintype "passive"))
      (node (ref "U42") (pin "84") (pinfunction "VDD_8_84") (pintype "passive"))
      (node (ref "U42") (pin "95") (pinfunction "VDD_9/VDDIO_1/VDD_USB33_95") (pintype "passive"))
    )
    (net (code "164") (name "unconnected-(L41-Pad1)") (class "Default")
      (node (ref "L41") (pin "1") (pinfunction "1_1") (pintype "passive+no_connect"))
    )
    (net (code "165") (name "unconnected-(L41-Pad2)") (class "Default")
      (node (ref "L41") (pin "2") (pinfunction "2_2") (pintype "passive+no_connect"))
    )
    (net (code "166") (name "unconnected-(U42B-PF12-Pad50)") (class "Default")
      (node (ref "U42") (pin "50") (pinfunction "PF12_50") (pintype "passive"))
    )
    (net (code "167") (name "unconnected-(U42B-PF13-Pad53)") (class "Default")
      (node (ref "U42") (pin "53") (pinfunction "PF13_53") (pintype "passive"))
    )
    (net (code "168") (name "unconnected-(U42B-PF14-Pad54)") (class "Default")
      (node (ref "U42") (pin "54") (pinfunction "PF14_54") (pintype "passive"))
    )
    (net (code "169") (name "unconnected-(U42B-PF15-Pad55)") (class "Default")
      (node (ref "U42") (pin "55") (pinfunction "PF15_55") (pintype "passive"))
    )
  )
)
